# Joystick_Shield-v10.net
KiCad netlist of a schematic drawn in EAGLE
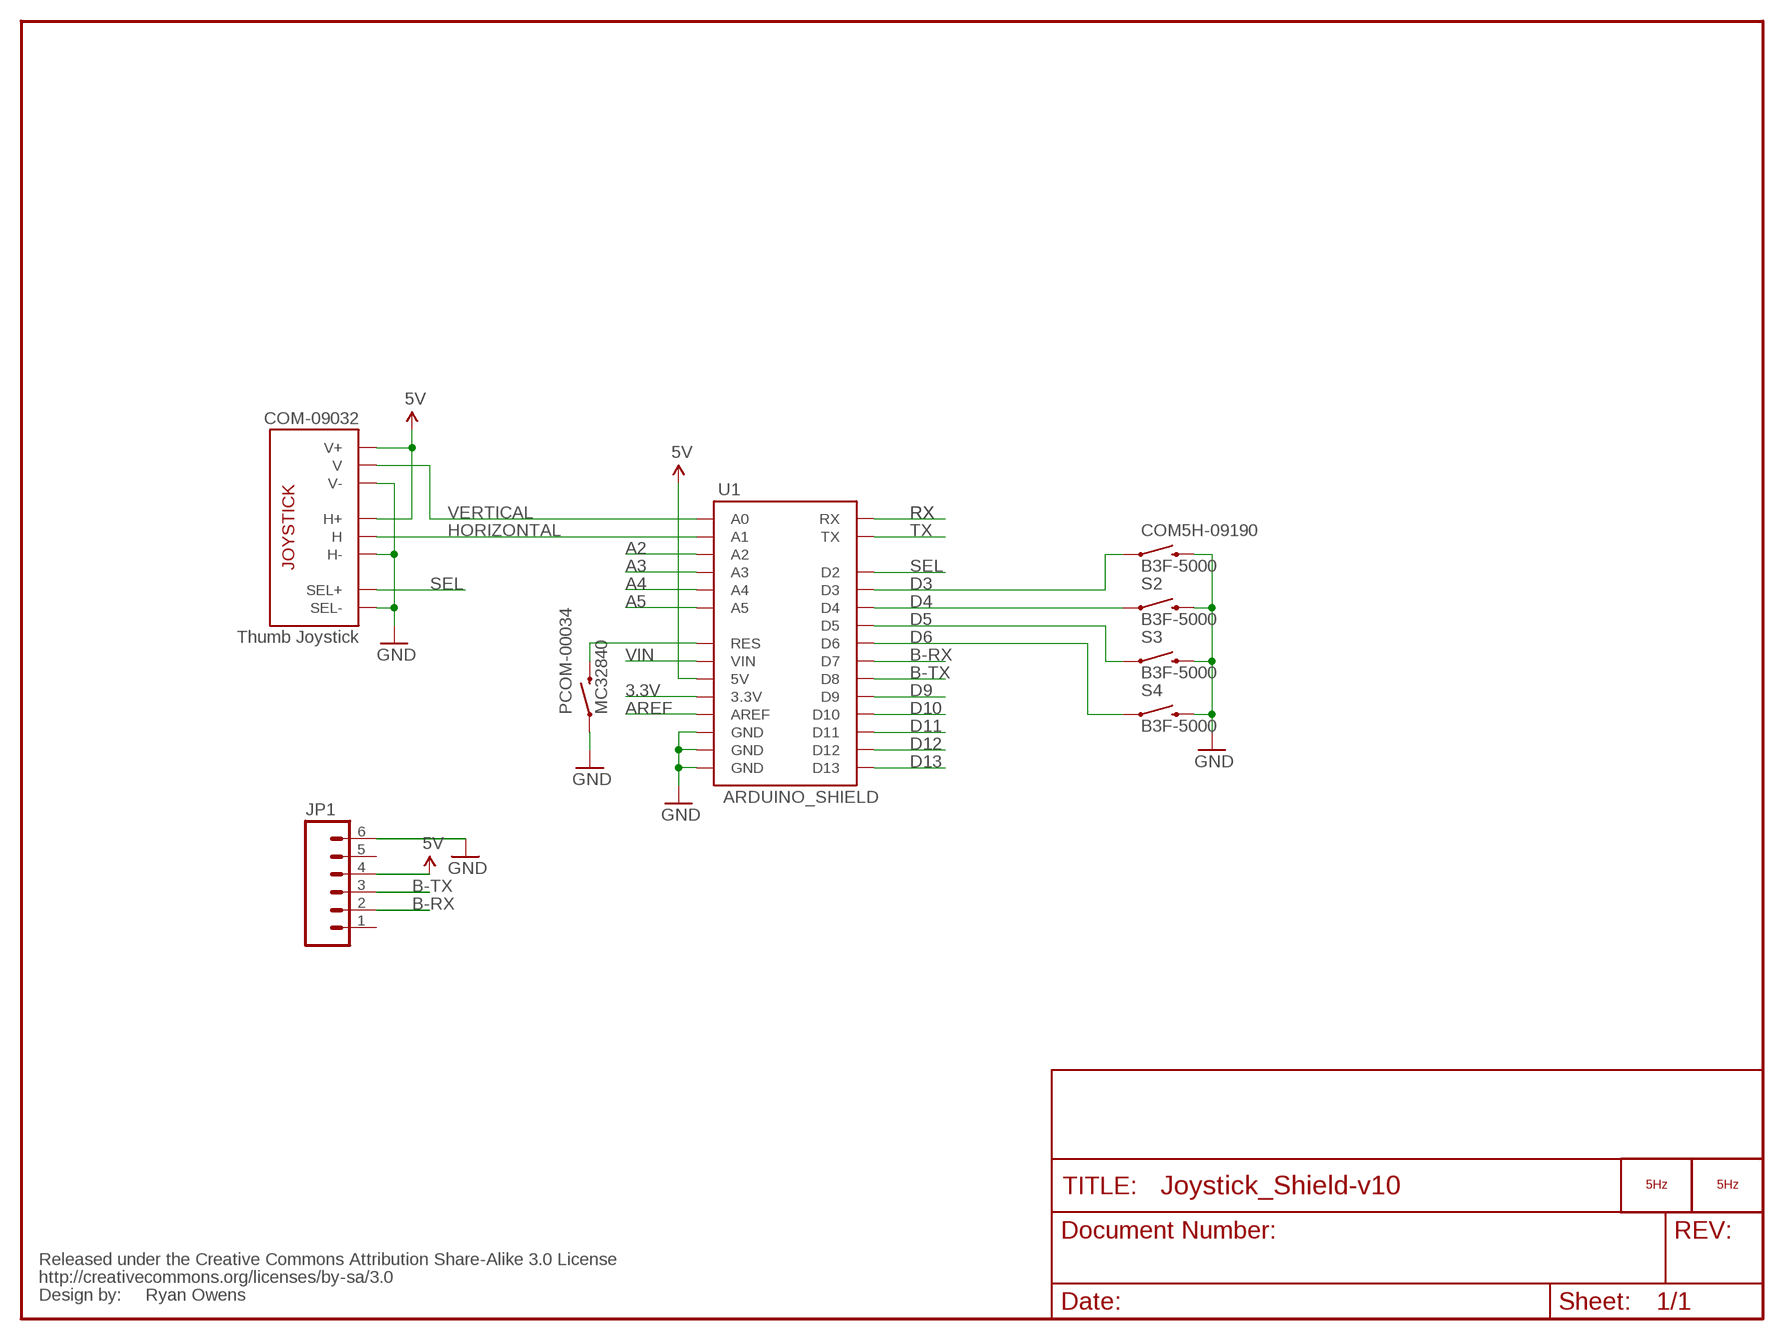
[diagram p0: schematic, sheet 1]

(export (version "E")
  (design (tool "Eeschema 10.0.6"))
  (components
    (comp (ref "COM-09032")
      (value "Thumb Joystick")
      (footprint "eagle-import:JOYSTICK")
      (libsource (lib "eagle-import") (part "JOYSTICKPTH"))
    )
    (comp (ref "COM5H-09190")
      (value "B3F-5000")
      (footprint "eagle-import:TACTILE-PTH-12MM")
      (libsource (lib "eagle-import") (part "SWITCH-MOMENTARY-212MM"))
    )
    (comp (ref "JP1")
      (value "M06SIP")
      (footprint "eagle-import:1X06")
      (libsource (lib "eagle-import") (part "M06SIP"))
    )
    (comp (ref "LOGO1")
      (value "LOGO_5HZ_H_COOPER_15MM")
      (footprint "eagle-import:5HZ_LOGO_H_COOPER_15MM")
      (libsource (lib "eagle-import") (part "LOGO_5HZ_H_COOPER_15MM"))
    )
    (comp (ref "LOGO2")
      (value "LOGO_5HZ_MAIN_15MM")
      (footprint "eagle-import:5HZ_LOGO_MAIN_15MM")
      (libsource (lib "eagle-import") (part "LOGO_5HZ_MAIN_15MM"))
    )
    (comp (ref "PCOM-00034")
      (value "MC32840")
      (footprint "eagle-import:TACTILE-PTH")
      (libsource (lib "eagle-import") (part "SWITCH-MOMENTARY-2PTH"))
    )
    (comp (ref "S2")
      (value "B3F-5000")
      (footprint "eagle-import:TACTILE-PTH-12MM")
      (libsource (lib "eagle-import") (part "SWITCH-MOMENTARY-212MM"))
    )
    (comp (ref "S3")
      (value "B3F-5000")
      (footprint "eagle-import:TACTILE-PTH-12MM")
      (libsource (lib "eagle-import") (part "SWITCH-MOMENTARY-212MM"))
    )
    (comp (ref "S4")
      (value "B3F-5000")
      (footprint "eagle-import:TACTILE-PTH-12MM")
      (libsource (lib "eagle-import") (part "SWITCH-MOMENTARY-212MM"))
    )
    (comp (ref "U$3")
      (value "CREATIVE_COMMONS")
      (footprint "eagle-import:CREATIVE_COMMONS")
      (libsource (lib "eagle-import") (part "CREATIVE_COMMONS"))
    )
    (comp (ref "U1")
      (value "ARDUINO_SHIELD")
      (footprint "eagle-import:DUEMILANOVE_SHIELD")
      (libsource (lib "eagle-import") (part "ARDUINO_SHIELDLABEL"))
    )
  )
  (nets
    (net (code "1") (name "/3.3V") (class "Default")
      (node (ref "U1") (pin "3.3V") (pinfunction "3.3V_3.3V") (pintype "bidirectional"))
    )
    (net (code "2") (name "/A2") (class "Default")
      (node (ref "U1") (pin "A2") (pinfunction "A2_A2") (pintype "bidirectional"))
    )
    (net (code "3") (name "/A3") (class "Default")
      (node (ref "U1") (pin "A3") (pinfunction "A3_A3") (pintype "bidirectional"))
    )
    (net (code "4") (name "/A4") (class "Default")
      (node (ref "U1") (pin "A4") (pinfunction "A4_A4") (pintype "bidirectional"))
    )
    (net (code "5") (name "/A5") (class "Default")
      (node (ref "U1") (pin "A5") (pinfunction "A5_A5") (pintype "bidirectional"))
    )
    (net (code "6") (name "/AREF") (class "Default")
      (node (ref "U1") (pin "AREF") (pinfunction "AREF_AREF") (pintype "bidirectional"))
    )
    (net (code "7") (name "/B-RX") (class "Default")
      (node (ref "JP1") (pin "2") (pinfunction "2_2") (pintype "passive"))
      (node (ref "U1") (pin "D7") (pinfunction "D7_D7") (pintype "bidirectional"))
    )
    (net (code "8") (name "/B-TX") (class "Default")
      (node (ref "JP1") (pin "3") (pinfunction "3_3") (pintype "passive"))
      (node (ref "U1") (pin "D8") (pinfunction "D8_D8") (pintype "bidirectional"))
    )
    (net (code "9") (name "/D3") (class "Default")
      (node (ref "COM5H-09190") (pin "1") (pinfunction "1_1") (pintype "passive"))
      (node (ref "U1") (pin "D3") (pinfunction "D3_D3") (pintype "bidirectional"))
    )
    (net (code "10") (name "/D4") (class "Default")
      (node (ref "S2") (pin "1") (pinfunction "1_1") (pintype "passive"))
      (node (ref "U1") (pin "D4") (pinfunction "D4_D4") (pintype "bidirectional"))
    )
    (net (code "11") (name "/D5") (class "Default")
      (node (ref "S3") (pin "1") (pinfunction "1_1") (pintype "passive"))
      (node (ref "U1") (pin "D5") (pinfunction "D5_D5") (pintype "bidirectional"))
    )
    (net (code "12") (name "/D6") (class "Default")
      (node (ref "S4") (pin "1") (pinfunction "1_1") (pintype "passive"))
      (node (ref "U1") (pin "D6") (pinfunction "D6_D6") (pintype "bidirectional"))
    )
    (net (code "13") (name "/D9") (class "Default")
      (node (ref "U1") (pin "D9") (pinfunction "D9_D9") (pintype "bidirectional"))
    )
    (net (code "14") (name "/D10") (class "Default")
      (node (ref "U1") (pin "D10") (pinfunction "D10_D10") (pintype "bidirectional"))
    )
    (net (code "15") (name "/D11") (class "Default")
      (node (ref "U1") (pin "D11") (pinfunction "D11_D11") (pintype "bidirectional"))
    )
    (net (code "16") (name "/D12") (class "Default")
      (node (ref "U1") (pin "D12") (pinfunction "D12_D12") (pintype "bidirectional"))
    )
    (net (code "17") (name "/D13") (class "Default")
      (node (ref "U1") (pin "D13") (pinfunction "D13_D13") (pintype "bidirectional"))
    )
    (net (code "18") (name "/HORIZONTAL") (class "Default")
      (node (ref "COM-09032") (pin "H2") (pinfunction "H_H2") (pintype "bidirectional"))
      (node (ref "U1") (pin "A1") (pinfunction "A1_A1") (pintype "bidirectional"))
    )
    (net (code "19") (name "/RX") (class "Default")
      (node (ref "U1") (pin "RX") (pinfunction "RX_RX") (pintype "bidirectional"))
    )
    (net (code "20") (name "/SEL") (class "Default")
      (node (ref "COM-09032") (pin "B1A") (pinfunction "SEL+_B1A") (pintype "bidirectional"))
      (node (ref "U1") (pin "D2") (pinfunction "D2_D2") (pintype "bidirectional"))
    )
    (net (code "21") (name "/TX") (class "Default")
      (node (ref "U1") (pin "TX") (pinfunction "TX_TX") (pintype "bidirectional"))
    )
    (net (code "22") (name "/VERTICAL") (class "Default")
      (node (ref "COM-09032") (pin "V2") (pinfunction "V_V2") (pintype "bidirectional"))
      (node (ref "U1") (pin "A0") (pinfunction "A0_A0") (pintype "bidirectional"))
    )
    (net (code "23") (name "/VIN") (class "Default")
      (node (ref "U1") (pin "VIN") (pinfunction "VIN_VIN") (pintype "bidirectional"))
    )
    (net (code "24") (name "5V") (class "Default")
      (node (ref "COM-09032") (pin "H1") (pinfunction "H+_H1") (pintype "bidirectional"))
      (node (ref "COM-09032") (pin "V1") (pinfunction "V+_V1") (pintype "bidirectional"))
      (node (ref "JP1") (pin "4") (pinfunction "4_4") (pintype "passive"))
      (node (ref "U1") (pin "5V") (pinfunction "5V_5V") (pintype "bidirectional"))
    )
    (net (code "25") (name "GND") (class "Default")
      (node (ref "COM-09032") (pin "B2A") (pinfunction "SEL-_B2A") (pintype "bidirectional"))
      (node (ref "COM-09032") (pin "H3") (pinfunction "H-_H3") (pintype "bidirectional"))
      (node (ref "COM-09032") (pin "V3") (pinfunction "V-_V3") (pintype "bidirectional"))
      (node (ref "COM5H-09190") (pin "3") (pinfunction "2_3") (pintype "passive"))
      (node (ref "JP1") (pin "6") (pinfunction "6_6") (pintype "passive"))
      (node (ref "PCOM-00034") (pin "1") (pinfunction "1_1") (pintype "passive"))
      (node (ref "S2") (pin "3") (pinfunction "2_3") (pintype "passive"))
      (node (ref "S3") (pin "3") (pinfunction "2_3") (pintype "passive"))
      (node (ref "S4") (pin "3") (pinfunction "2_3") (pintype "passive"))
      (node (ref "U1") (pin "GND@0") (pinfunction "GND_GND@0") (pintype "bidirectional"))
      (node (ref "U1") (pin "GND@1") (pinfunction "GND_GND@1") (pintype "bidirectional"))
      (node (ref "U1") (pin "GND@2") (pinfunction "GND_GND@2") (pintype "bidirectional"))
    )
    (net (code "26") (name "Net-(PCOM-00034-2)") (class "Default")
      (node (ref "PCOM-00034") (pin "3") (pinfunction "2_3") (pintype "passive"))
      (node (ref "U1") (pin "RES") (pinfunction "RES_RES") (pintype "bidirectional"))
    )
    (net (code "27") (name "unconnected-(JP1-Pad1)") (class "Default")
      (node (ref "JP1") (pin "1") (pinfunction "1_1") (pintype "passive"))
    )
    (net (code "28") (name "unconnected-(JP1-Pad5)") (class "Default")
      (node (ref "JP1") (pin "5") (pinfunction "5_5") (pintype "passive"))
    )
  )
)
